# rpipowerhat.net
KiCad netlist of a schematic drawn in EAGLE
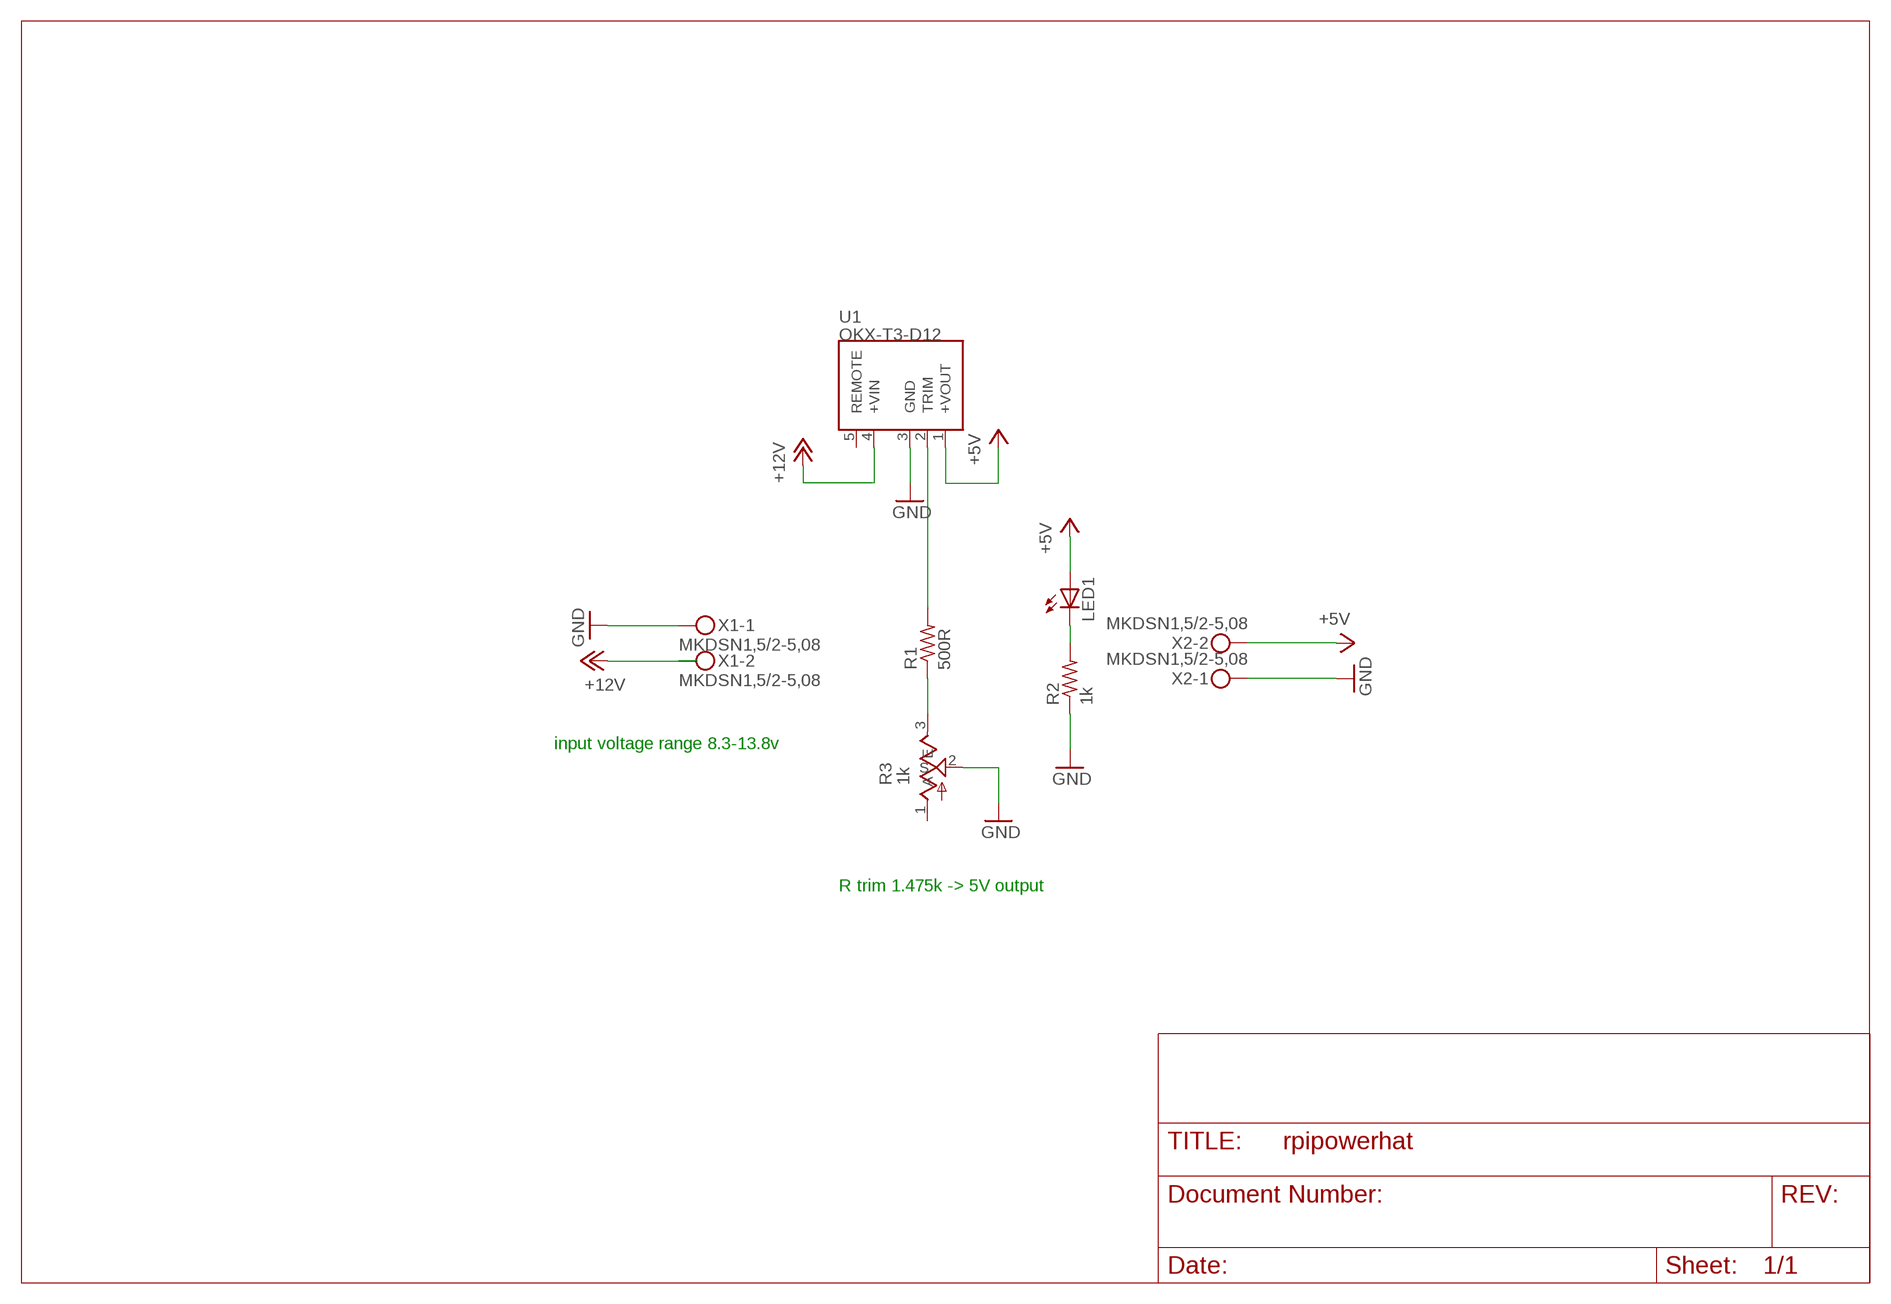
[diagram p0: schematic, sheet 1]

(export (version "E")
  (design (tool "Eeschema 10.0.6"))
  (components
    (comp (ref "LED1")
      (value "LEDCHIPLED_0603")
      (footprint "eagle-import:CHIPLED_0603")
      (libsource (lib "eagle-import") (part "LEDCHIPLED_0603"))
    )
    (comp (ref "R1")
      (value "500R")
      (footprint "eagle-import:R0603")
      (libsource (lib "eagle-import") (part "R-US_R0603"))
    )
    (comp (ref "R2")
      (value "1k")
      (footprint "eagle-import:R0603")
      (libsource (lib "eagle-import") (part "R-US_R0603"))
    )
    (comp (ref "R3")
      (value "1k")
      (footprint "eagle-import:RTRIM3296W")
      (libsource (lib "eagle-import") (part "POT-3296"))
    )
    (comp (ref "U1")
      (value "OKX-T3-D12")
      (footprint "eagle-import:OKX-T3-D12")
      (libsource (lib "eagle-import") (part "OKX-T3-D12"))
    )
    (comp (ref "X1")
      (value "MKDSN1,5/2-5,08")
      (footprint "eagle-import:MKDSN1,5_2-5,08")
      (libsource (lib "eagle-import") (part "MKDSN1,5/2-5,08"))
    )
    (comp (ref "X2")
      (value "MKDSN1,5/2-5,08")
      (footprint "eagle-import:MKDSN1,5_2-5,08")
      (libsource (lib "eagle-import") (part "MKDSN1,5/2-5,08"))
    )
  )
  (nets
    (net (code "1") (name "+5V") (class "Default")
      (node (ref "LED1") (pin "A") (pinfunction "A_A") (pintype "passive"))
      (node (ref "U1") (pin "1") (pinfunction "+VOUT_1") (pintype "bidirectional"))
      (node (ref "X2") (pin "2") (pinfunction "KL_2") (pintype "passive"))
    )
    (net (code "2") (name "+12V") (class "Default")
      (node (ref "U1") (pin "4") (pinfunction "+VIN_4") (pintype "bidirectional"))
      (node (ref "X1") (pin "2") (pinfunction "KL_2") (pintype "passive"))
    )
    (net (code "3") (name "GND") (class "Default")
      (node (ref "R2") (pin "1") (pinfunction "1_1") (pintype "passive"))
      (node (ref "R3") (pin "2") (pinfunction "S_2") (pintype "passive"))
      (node (ref "U1") (pin "3") (pinfunction "GND_3") (pintype "bidirectional"))
      (node (ref "X1") (pin "1") (pinfunction "KL_1") (pintype "passive"))
      (node (ref "X2") (pin "1") (pinfunction "KL_1") (pintype "passive"))
    )
    (net (code "4") (name "Net-(LED1-PadC)") (class "Default")
      (node (ref "LED1") (pin "C") (pinfunction "C_C") (pintype "passive"))
      (node (ref "R2") (pin "2") (pinfunction "2_2") (pintype "passive"))
    )
    (net (code "5") (name "Net-(R3-E)") (class "Default")
      (node (ref "R1") (pin "1") (pinfunction "1_1") (pintype "passive"))
      (node (ref "R3") (pin "3") (pinfunction "E_3") (pintype "passive"))
    )
    (net (code "6") (name "Net-(U1-TRIM)") (class "Default")
      (node (ref "R1") (pin "2") (pinfunction "2_2") (pintype "passive"))
      (node (ref "U1") (pin "2") (pinfunction "TRIM_2") (pintype "bidirectional"))
    )
    (net (code "7") (name "unconnected-(R3-A-Pad1)") (class "Default")
      (node (ref "R3") (pin "1") (pinfunction "A_1") (pintype "passive"))
    )
    (net (code "8") (name "unconnected-(U1-REMOTE-Pad5)") (class "Default")
      (node (ref "U1") (pin "5") (pinfunction "REMOTE_5") (pintype "bidirectional"))
    )
  )
)
